# 07_SD_QSPI.net
KiCad netlist of a schematic drawn in Altium Designer
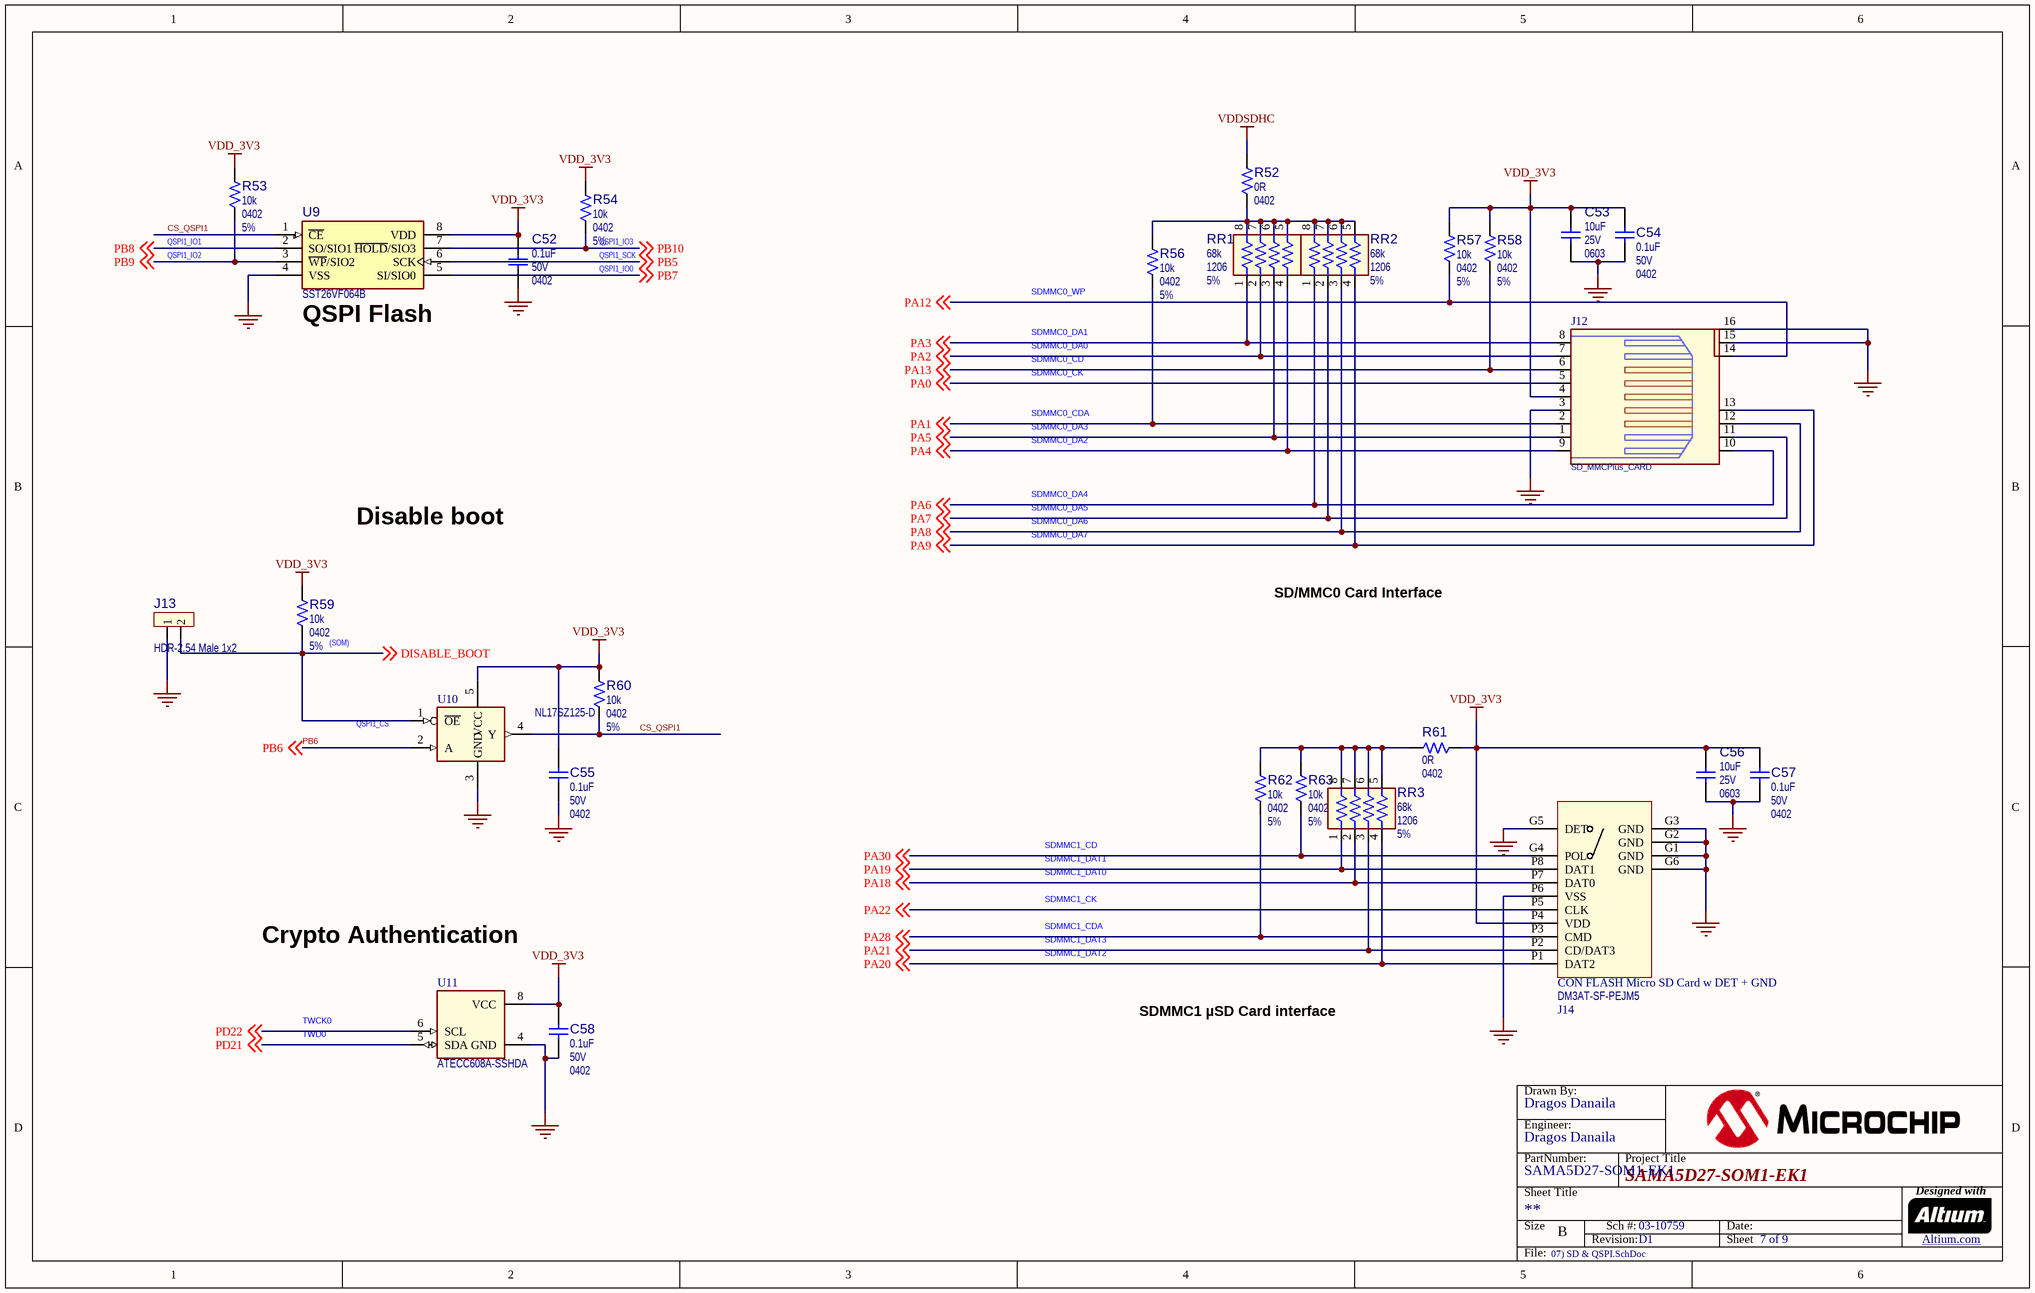
[diagram p0: 07) SD & QSPI.SchDoc]

(export (version "E")
  (design (tool "Eeschema 10.0.6"))
  (components
    (comp (ref "C52")
      (value "0.1uF")
      (footprint "CAP_C_0402")
      (description "Capacitor")
      (fields
        (field (name "VOLTAGE") "50V")
        (field (name "PACKAGE") "0402")
        (field (name "TOLERANCE") "10%")
        (field (name "Comment") "Capacitor NP")
        (field (name "OWNER") "Jamus Griego")
      )
      (libsource (lib "MCHP-CDB") (part "Capacitor NP"))
    )
    (comp (ref "C53")
      (value "10uF")
      (footprint "CAP_C_0603")
      (description "Capacitor")
      (fields
        (field (name "VOLTAGE") "25V")
        (field (name "PACKAGE") "0603")
        (field (name "TOLERANCE") "20%")
        (field (name "Comment") "Capacitor NP")
        (field (name "OWNER") "Razvan Cristescu")
      )
      (libsource (lib "MCHP-CDB") (part "Capacitor NP"))
    )
    (comp (ref "C54")
      (value "0.1uF")
      (footprint "CAP_C_0402")
      (description "Capacitor")
      (fields
        (field (name "VOLTAGE") "50V")
        (field (name "PACKAGE") "0402")
        (field (name "TOLERANCE") "10%")
        (field (name "Comment") "Capacitor NP")
        (field (name "OWNER") "Jamus Griego")
      )
      (libsource (lib "MCHP-CDB") (part "Capacitor NP"))
    )
    (comp (ref "C55")
      (value "0.1uF")
      (footprint "CAP_C_0402")
      (description "Capacitor")
      (fields
        (field (name "VOLTAGE") "50V")
        (field (name "PACKAGE") "0402")
        (field (name "TOLERANCE") "10%")
        (field (name "Comment") "Capacitor NP")
        (field (name "OWNER") "Jamus Griego")
      )
      (libsource (lib "MCHP-CDB") (part "Capacitor NP"))
    )
    (comp (ref "C56")
      (value "10uF")
      (footprint "CAP_C_0603")
      (description "Capacitor")
      (fields
        (field (name "VOLTAGE") "25V")
        (field (name "PACKAGE") "0603")
        (field (name "TOLERANCE") "20%")
        (field (name "Comment") "Capacitor NP")
        (field (name "OWNER") "Razvan Cristescu")
      )
      (libsource (lib "MCHP-CDB") (part "Capacitor NP"))
    )
    (comp (ref "C57")
      (value "0.1uF")
      (footprint "CAP_C_0402")
      (description "Capacitor")
      (fields
        (field (name "VOLTAGE") "50V")
        (field (name "PACKAGE") "0402")
        (field (name "TOLERANCE") "10%")
        (field (name "Comment") "Capacitor NP")
        (field (name "OWNER") "Jamus Griego")
      )
      (libsource (lib "MCHP-CDB") (part "Capacitor NP"))
    )
    (comp (ref "C58")
      (value "0.1uF")
      (footprint "CAP_C_0402")
      (description "Capacitor")
      (fields
        (field (name "VOLTAGE") "50V")
        (field (name "PACKAGE") "0402")
        (field (name "TOLERANCE") "10%")
        (field (name "Comment") "Capacitor NP")
        (field (name "OWNER") "Jamus Griego")
      )
      (libsource (lib "MCHP-CDB") (part "Capacitor NP"))
    )
    (comp (ref "J12")
      (value "SD_MMCPlus_CARD")
      (footprint "7SDMM-X0-2211")
      (description "5 IN 1 CARD CONNECTOR(SD & MMC")
      (fields (field (name "OWNER") "Dragos Danaila"))
      (libsource (lib "MCHP-CDB") (part "SD_MMCPlus_CARD"))
    )
    (comp (ref "J13")
      (value "HDR-2.54 Male 1x2")
      (footprint "HDR_M_2.54_1x2")
      (fields (field (name "Comment") "Header 1x2") (field (name "OWNER") "Bogdan P (M91398)"))
      (libsource (lib "MCHP-CDB") (part "Header 1x2"))
    )
    (comp (ref "J14")
      (value "CON FLASH Micro SD Card w DET + GND")
      (footprint "CON FLASH microSD 8+2P Push-Push SMD")
      (fields
        (field (name "ALTIUM_VALUE") "DM3AT-SF-PEJM5")
        (field (name "VOLTAGE") "125VAC")
        (field (name "OWNER") "Dragos Danaila")
      )
      (libsource (lib "MCHP-CDB") (part "CON FLASH Micro SD Card w DET + GND"))
    )
    (comp (ref "R52")
      (value "0R")
      (footprint "RES_C_0402")
      (description "Resistor")
      (fields (field (name "PACKAGE") "0402") (field (name "POWER") "1/10W"))
      (libsource (lib "MCHP-CDB") (part "Resistor"))
    )
    (comp (ref "R53")
      (value "10k")
      (footprint "RES_C_0402")
      (description "Resistor")
      (fields
        (field (name "PACKAGE") "0402")
        (field (name "TOLERANCE") "5%")
        (field (name "VOLTAGE") "50V")
        (field (name "POWER") "1/16W")
      )
      (libsource (lib "MCHP-CDB") (part "Resistor"))
    )
    (comp (ref "R54")
      (value "10k")
      (footprint "RES_C_0402")
      (description "Resistor")
      (fields
        (field (name "PACKAGE") "0402")
        (field (name "TOLERANCE") "5%")
        (field (name "VOLTAGE") "50V")
        (field (name "POWER") "1/16W")
      )
      (libsource (lib "MCHP-CDB") (part "Resistor"))
    )
    (comp (ref "R56")
      (value "10k")
      (footprint "RES_C_0402")
      (description "Resistor")
      (fields
        (field (name "PACKAGE") "0402")
        (field (name "TOLERANCE") "5%")
        (field (name "VOLTAGE") "50V")
        (field (name "POWER") "1/16W")
      )
      (libsource (lib "MCHP-CDB") (part "Resistor"))
    )
    (comp (ref "R57")
      (value "10k")
      (footprint "RES_C_0402")
      (description "Resistor")
      (fields
        (field (name "PACKAGE") "0402")
        (field (name "TOLERANCE") "5%")
        (field (name "VOLTAGE") "50V")
        (field (name "POWER") "1/16W")
      )
      (libsource (lib "MCHP-CDB") (part "Resistor"))
    )
    (comp (ref "R58")
      (value "10k")
      (footprint "RES_C_0402")
      (description "Resistor")
      (fields
        (field (name "PACKAGE") "0402")
        (field (name "TOLERANCE") "5%")
        (field (name "VOLTAGE") "50V")
        (field (name "POWER") "1/16W")
      )
      (libsource (lib "MCHP-CDB") (part "Resistor"))
    )
    (comp (ref "R59")
      (value "10k")
      (footprint "RES_C_0402")
      (description "Resistor")
      (fields
        (field (name "PACKAGE") "0402")
        (field (name "TOLERANCE") "5%")
        (field (name "VOLTAGE") "50V")
        (field (name "POWER") "1/16W")
      )
      (libsource (lib "MCHP-CDB") (part "Resistor"))
    )
    (comp (ref "R60")
      (value "10k")
      (footprint "RES_C_0402")
      (description "Resistor")
      (fields
        (field (name "PACKAGE") "0402")
        (field (name "TOLERANCE") "5%")
        (field (name "VOLTAGE") "50V")
        (field (name "POWER") "1/16W")
      )
      (libsource (lib "MCHP-CDB") (part "Resistor"))
    )
    (comp (ref "R61")
      (value "0R")
      (footprint "RES_C_0402")
      (description "Resistor")
      (fields (field (name "PACKAGE") "0402") (field (name "POWER") "1/10W"))
      (libsource (lib "MCHP-CDB") (part "Resistor"))
    )
    (comp (ref "R62")
      (value "10k")
      (footprint "RES_C_0402")
      (description "Resistor")
      (fields
        (field (name "PACKAGE") "0402")
        (field (name "TOLERANCE") "5%")
        (field (name "VOLTAGE") "50V")
        (field (name "POWER") "1/16W")
      )
      (libsource (lib "MCHP-CDB") (part "Resistor"))
    )
    (comp (ref "R63")
      (value "10k")
      (footprint "RES_C_0402")
      (description "Resistor")
      (fields
        (field (name "PACKAGE") "0402")
        (field (name "TOLERANCE") "5%")
        (field (name "VOLTAGE") "50V")
        (field (name "POWER") "1/16W")
      )
      (libsource (lib "MCHP-CDB") (part "Resistor"))
    )
    (comp (ref "RR1")
      (value "68k")
      (footprint "RES_C_CAV_0603x4")
      (description "Resistor")
      (fields
        (field (name "PACKAGE") "1206")
        (field (name "TOLERANCE") "5%")
        (field (name "VOLTAGE") "50V")
        (field (name "POWER") "62.5mW")
        (field (name "OWNER") "Alexandru Chiser - M19201")
      )
      (libsource (lib "MCHP-CDB") (part "Resistor Network 4-Ch"))
    )
    (comp (ref "RR2")
      (value "68k")
      (footprint "RES_C_CAV_0603x4")
      (description "Resistor")
      (fields
        (field (name "PACKAGE") "1206")
        (field (name "TOLERANCE") "5%")
        (field (name "VOLTAGE") "50V")
        (field (name "POWER") "62.5mW")
        (field (name "OWNER") "Alexandru Chiser - M19201")
      )
      (libsource (lib "MCHP-CDB") (part "Resistor Network 4-Ch"))
    )
    (comp (ref "RR3")
      (value "68k")
      (footprint "RES_C_CAV_0603x4")
      (description "Resistor")
      (fields
        (field (name "PACKAGE") "1206")
        (field (name "TOLERANCE") "5%")
        (field (name "VOLTAGE") "50V")
        (field (name "POWER") "62.5mW")
        (field (name "OWNER") "Alexandru Chiser - M19201")
      )
      (libsource (lib "MCHP-CDB") (part "Resistor Network 4-Ch"))
    )
    (comp (ref "U9")
      (value "SST26VF064B")
      (footprint "SOIJ-8")
      (description "SQI Serial Flash")
      (fields
        (field (name "Comment") "SST26VFXXX SOIC-8_WSON-8_SOIJ-8")
        (field (name "OWNER") "Sompoch Loboonlert")
      )
      (libsource (lib "MCHP-CDB") (part "SST26VFXXX SOIC-8_WSON-8_SOIJ-8"))
    )
    (comp (ref "U10")
      (value "NL17SZ125-D")
      (footprint "SOT-353")
      (fields
        (field (name "Comment") "NL17SZ125-D SOT-353")
        (field (name "OWNER") "Alexandru Chiser - M19201")
      )
      (libsource (lib "MCHP-CDB") (part "NL17SZ125-D SOT-353"))
    )
    (comp (ref "U11")
      (value "ATECC608A-SSHDA")
      (footprint "SOIC-8")
      (fields (field (name "Comment") "ATECC608A-SSHDA-B SOIC-8") (field (name "OWNER") "Mark Loper"))
      (libsource (lib "MCHP-CDB") (part "ATECC608A-SSHDA-B SOIC-8"))
    )
  )
  (nets
    (net (code "1") (name "/CS_QSPI1") (class "Default")
      (node (ref "R60") (pin "2") (pinfunction "2_2") (pintype "passive"))
      (node (ref "U10") (pin "4") (pinfunction "Y_4") (pintype "output"))
      (node (ref "U9") (pin "1") (pinfunction "~{CE}_1") (pintype "input"))
    )
    (net (code "2") (name "DISABLE_BOOT") (class "Default")
      (node (ref "J13") (pin "2") (pinfunction "2_2") (pintype "passive"))
      (node (ref "R59") (pin "2") (pinfunction "2_2") (pintype "passive"))
      (node (ref "U10") (pin "1") (pinfunction "~{OE}_1") (pintype "input"))
    )
    (net (code "3") (name "GND_POWER") (class "Default")
      (node (ref "C52") (pin "2") (pinfunction "2_2") (pintype "passive"))
      (node (ref "C53") (pin "2") (pinfunction "2_2") (pintype "passive"))
      (node (ref "C54") (pin "2") (pinfunction "2_2") (pintype "passive"))
      (node (ref "C55") (pin "2") (pinfunction "2_2") (pintype "passive"))
      (node (ref "C56") (pin "2") (pinfunction "2_2") (pintype "passive"))
      (node (ref "C57") (pin "2") (pinfunction "2_2") (pintype "passive"))
      (node (ref "C58") (pin "2") (pinfunction "2_2") (pintype "passive"))
      (node (ref "J12") (pin "15") (pinfunction "GND_15") (pintype "passive"))
      (node (ref "J12") (pin "16") (pinfunction "NC_16") (pintype "passive"))
      (node (ref "J12") (pin "3") (pinfunction "3_3") (pintype "passive"))
      (node (ref "J13") (pin "1") (pinfunction "1_1") (pintype "passive"))
      (node (ref "J14") (pin "G1") (pinfunction "GND_G1") (pintype "power_in"))
      (node (ref "J14") (pin "G2") (pinfunction "GND_G2") (pintype "power_in"))
      (node (ref "J14") (pin "G3") (pinfunction "GND_G3") (pintype "power_in"))
      (node (ref "J14") (pin "G5") (pinfunction "DET_G5") (pintype "passive"))
      (node (ref "J14") (pin "G6") (pinfunction "GND_G6") (pintype "power_in"))
      (node (ref "J14") (pin "P6") (pinfunction "VSS_P6") (pintype "power_in"))
      (node (ref "U10") (pin "3") (pinfunction "GND_3") (pintype "passive"))
      (node (ref "U11") (pin "4") (pinfunction "GND_4") (pintype "power_in"))
      (node (ref "U9") (pin "4") (pinfunction "VSS_4") (pintype "power_in"))
    )
    (net (code "4") (name "Net-(R52-Pad2)") (class "Default")
      (node (ref "R52") (pin "2") (pinfunction "2_2") (pintype "passive"))
      (node (ref "R56") (pin "1") (pinfunction "1_1") (pintype "passive"))
      (node (ref "RR1") (pin "5") (pinfunction "5_5") (pintype "passive"))
      (node (ref "RR1") (pin "6") (pinfunction "6_6") (pintype "passive"))
      (node (ref "RR1") (pin "7") (pinfunction "7_7") (pintype "passive"))
      (node (ref "RR1") (pin "8") (pinfunction "8_8") (pintype "passive"))
      (node (ref "RR2") (pin "5") (pinfunction "5_5") (pintype "passive"))
      (node (ref "RR2") (pin "6") (pinfunction "6_6") (pintype "passive"))
      (node (ref "RR2") (pin "7") (pinfunction "7_7") (pintype "passive"))
      (node (ref "RR2") (pin "8") (pinfunction "8_8") (pintype "passive"))
    )
    (net (code "5") (name "Net-(R61-Pad1)") (class "Default")
      (node (ref "R61") (pin "1") (pinfunction "1_1") (pintype "passive"))
      (node (ref "R62") (pin "1") (pinfunction "1_1") (pintype "passive"))
      (node (ref "R63") (pin "1") (pinfunction "1_1") (pintype "passive"))
      (node (ref "RR3") (pin "5") (pinfunction "5_5") (pintype "passive"))
      (node (ref "RR3") (pin "6") (pinfunction "6_6") (pintype "passive"))
      (node (ref "RR3") (pin "7") (pinfunction "7_7") (pintype "passive"))
      (node (ref "RR3") (pin "8") (pinfunction "8_8") (pintype "passive"))
    )
    (net (code "6") (name "PA0") (class "Default")
      (node (ref "J12") (pin "5") (pinfunction "5_5") (pintype "passive"))
    )
    (net (code "7") (name "PA1") (class "Default")
      (node (ref "J12") (pin "2") (pinfunction "2_2") (pintype "passive"))
      (node (ref "R56") (pin "2") (pinfunction "2_2") (pintype "passive"))
    )
    (net (code "8") (name "PA2") (class "Default")
      (node (ref "J12") (pin "7") (pinfunction "7_7") (pintype "passive"))
      (node (ref "RR1") (pin "2") (pinfunction "2_2") (pintype "passive"))
    )
    (net (code "9") (name "PA3") (class "Default")
      (node (ref "J12") (pin "8") (pinfunction "8_8") (pintype "passive"))
      (node (ref "RR1") (pin "1") (pinfunction "1_1") (pintype "passive"))
    )
    (net (code "10") (name "PA4") (class "Default")
      (node (ref "J12") (pin "9") (pinfunction "9_9") (pintype "passive"))
      (node (ref "RR1") (pin "4") (pinfunction "4_4") (pintype "passive"))
    )
    (net (code "11") (name "PA5") (class "Default")
      (node (ref "J12") (pin "1") (pinfunction "1_1") (pintype "passive"))
      (node (ref "RR1") (pin "3") (pinfunction "3_3") (pintype "passive"))
    )
    (net (code "12") (name "PA6") (class "Default")
      (node (ref "J12") (pin "10") (pinfunction "10_10") (pintype "passive"))
      (node (ref "RR2") (pin "1") (pinfunction "1_1") (pintype "passive"))
    )
    (net (code "13") (name "PA7") (class "Default")
      (node (ref "J12") (pin "11") (pinfunction "11_11") (pintype "passive"))
      (node (ref "RR2") (pin "2") (pinfunction "2_2") (pintype "passive"))
    )
    (net (code "14") (name "PA8") (class "Default")
      (node (ref "J12") (pin "12") (pinfunction "12_12") (pintype "passive"))
      (node (ref "RR2") (pin "3") (pinfunction "3_3") (pintype "passive"))
    )
    (net (code "15") (name "PA9") (class "Default")
      (node (ref "J12") (pin "13") (pinfunction "13_13") (pintype "passive"))
      (node (ref "RR2") (pin "4") (pinfunction "4_4") (pintype "passive"))
    )
    (net (code "16") (name "PA12") (class "Default")
      (node (ref "J12") (pin "14") (pinfunction "WP_14") (pintype "passive"))
      (node (ref "R57") (pin "2") (pinfunction "2_2") (pintype "passive"))
    )
    (net (code "17") (name "PA13") (class "Default")
      (node (ref "J12") (pin "6") (pinfunction "6_6") (pintype "passive"))
      (node (ref "R58") (pin "2") (pinfunction "2_2") (pintype "passive"))
    )
    (net (code "18") (name "PA18") (class "Default")
      (node (ref "J14") (pin "P7") (pinfunction "DAT0_P7") (pintype "passive"))
      (node (ref "RR3") (pin "2") (pinfunction "2_2") (pintype "passive"))
    )
    (net (code "19") (name "PA19") (class "Default")
      (node (ref "J14") (pin "P8") (pinfunction "DAT1_P8") (pintype "passive"))
      (node (ref "RR3") (pin "1") (pinfunction "1_1") (pintype "passive"))
    )
    (net (code "20") (name "PA20") (class "Default")
      (node (ref "J14") (pin "P1") (pinfunction "DAT2_P1") (pintype "passive"))
      (node (ref "RR3") (pin "4") (pinfunction "4_4") (pintype "passive"))
    )
    (net (code "21") (name "PA21") (class "Default")
      (node (ref "J14") (pin "P2") (pinfunction "CD/DAT3_P2") (pintype "passive"))
      (node (ref "RR3") (pin "3") (pinfunction "3_3") (pintype "passive"))
    )
    (net (code "22") (name "PA22") (class "Default")
      (node (ref "J14") (pin "P5") (pinfunction "CLK_P5") (pintype "passive"))
    )
    (net (code "23") (name "PA28") (class "Default")
      (node (ref "J14") (pin "P3") (pinfunction "CMD_P3") (pintype "passive"))
      (node (ref "R62") (pin "2") (pinfunction "2_2") (pintype "passive"))
    )
    (net (code "24") (name "PA30") (class "Default")
      (node (ref "J14") (pin "G4") (pinfunction "POL_G4") (pintype "passive"))
      (node (ref "R63") (pin "2") (pinfunction "2_2") (pintype "passive"))
    )
    (net (code "25") (name "PB5") (class "Default")
      (node (ref "U9") (pin "6") (pinfunction "SCK_6") (pintype "input"))
    )
    (net (code "26") (name "PB6") (class "Default")
      (node (ref "U10") (pin "2") (pinfunction "A_2") (pintype "input"))
    )
    (net (code "27") (name "PB7") (class "Default")
      (node (ref "U9") (pin "5") (pinfunction "SI/SIO0_5") (pintype "passive"))
    )
    (net (code "28") (name "PB8") (class "Default")
      (node (ref "U9") (pin "2") (pinfunction "SO/SIO1_2") (pintype "passive"))
    )
    (net (code "29") (name "PB9") (class "Default")
      (node (ref "R53") (pin "2") (pinfunction "2_2") (pintype "passive"))
      (node (ref "U9") (pin "3") (pinfunction "~{WP}/SIO2_3") (pintype "passive"))
    )
    (net (code "30") (name "PB10") (class "Default")
      (node (ref "R54") (pin "2") (pinfunction "2_2") (pintype "passive"))
      (node (ref "U9") (pin "7") (pinfunction "~{HOLD}/SIO3_7") (pintype "passive"))
    )
    (net (code "31") (name "PD21") (class "Default")
      (node (ref "U11") (pin "5") (pinfunction "SDA_5") (pintype "bidirectional"))
    )
    (net (code "32") (name "PD22") (class "Default")
      (node (ref "U11") (pin "6") (pinfunction "SCL_6") (pintype "input"))
    )
    (net (code "33") (name "VDDSDHC") (class "Default")
      (node (ref "R52") (pin "1") (pinfunction "1_1") (pintype "passive"))
    )
    (net (code "34") (name "VDD_3V3") (class "Default")
      (node (ref "C52") (pin "1") (pinfunction "1_1") (pintype "passive"))
      (node (ref "C53") (pin "1") (pinfunction "1_1") (pintype "passive"))
      (node (ref "C54") (pin "1") (pinfunction "1_1") (pintype "passive"))
      (node (ref "C55") (pin "1") (pinfunction "1_1") (pintype "passive"))
      (node (ref "C56") (pin "1") (pinfunction "1_1") (pintype "passive"))
      (node (ref "C57") (pin "1") (pinfunction "1_1") (pintype "passive"))
      (node (ref "C58") (pin "1") (pinfunction "1_1") (pintype "passive"))
      (node (ref "J12") (pin "4") (pinfunction "4_4") (pintype "passive"))
      (node (ref "J14") (pin "P4") (pinfunction "VDD_P4") (pintype "power_in"))
      (node (ref "R53") (pin "1") (pinfunction "1_1") (pintype "passive"))
      (node (ref "R54") (pin "1") (pinfunction "1_1") (pintype "passive"))
      (node (ref "R57") (pin "1") (pinfunction "1_1") (pintype "passive"))
      (node (ref "R58") (pin "1") (pinfunction "1_1") (pintype "passive"))
      (node (ref "R59") (pin "1") (pinfunction "1_1") (pintype "passive"))
      (node (ref "R60") (pin "1") (pinfunction "1_1") (pintype "passive"))
      (node (ref "R61") (pin "2") (pinfunction "2_2") (pintype "passive"))
      (node (ref "U10") (pin "5") (pinfunction "VCC_5") (pintype "power_in"))
      (node (ref "U11") (pin "8") (pinfunction "VCC_8") (pintype "power_in"))
      (node (ref "U9") (pin "8") (pinfunction "VDD_8") (pintype "power_in"))
    )
  )
)
